# 01-SNESDRONE_Direct_IO_PSU.net
KiCad netlist of a schematic drawn in Altium Designer
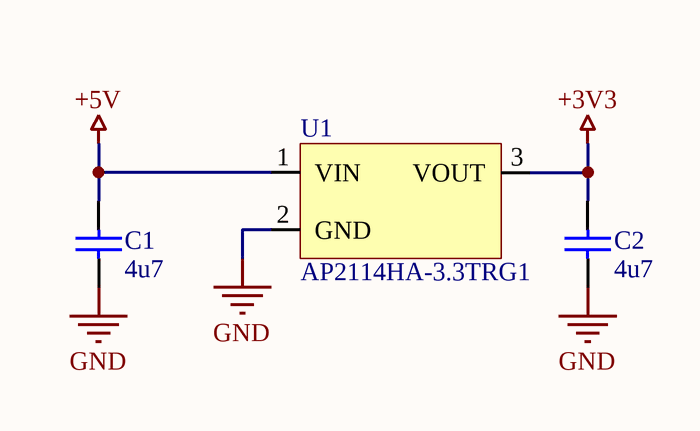
[diagram p0: 01-SNESDRONE_Direct_IO_PSU.SchDoc]

(export (version "E")
  (design (tool "Eeschema 10.0.6"))
  (components
    (comp (ref "C1")
      (value "4u7")
      (footprint "cap_0603")
      (description "Capacitor")
      (fields (field (name "Comment") "cap_0603"))
      (libsource (lib "mycomponents") (part "cap_0603"))
    )
    (comp (ref "C2")
      (value "4u7")
      (footprint "cap_0603")
      (description "Capacitor")
      (fields (field (name "Comment") "cap_0603"))
      (libsource (lib "mycomponents") (part "cap_0603"))
    )
    (comp (ref "U1")
      (value "AP2114HA-3.3TRG1")
      (footprint "SOT223")
      (description "PMIC - Spannungsregler - Linear Positiv Fest 1 Ausgang 1A SOT-223-3")
      (libsource (lib "mycomponents") (part "AP2114HA-3.3TRG1"))
    )
  )
  (nets
    (net (code "1") (name "+3V3") (class "Default")
      (node (ref "C2") (pin "2") (pinfunction "2_2") (pintype "passive"))
      (node (ref "U1") (pin "3") (pinfunction "VOUT_3") (pintype "passive"))
    )
    (net (code "2") (name "+5V") (class "Default")
      (node (ref "C1") (pin "2") (pinfunction "2_2") (pintype "passive"))
      (node (ref "U1") (pin "1") (pinfunction "VIN_1") (pintype "passive"))
    )
    (net (code "3") (name "GND") (class "Default")
      (node (ref "C1") (pin "1") (pinfunction "1_1") (pintype "passive"))
      (node (ref "C2") (pin "1") (pinfunction "1_1") (pintype "passive"))
      (node (ref "U1") (pin "2") (pinfunction "GND_2") (pintype "passive"))
    )
  )
)
